# supply-protection.net
KiCad netlist of a schematic drawn in Altium Designer
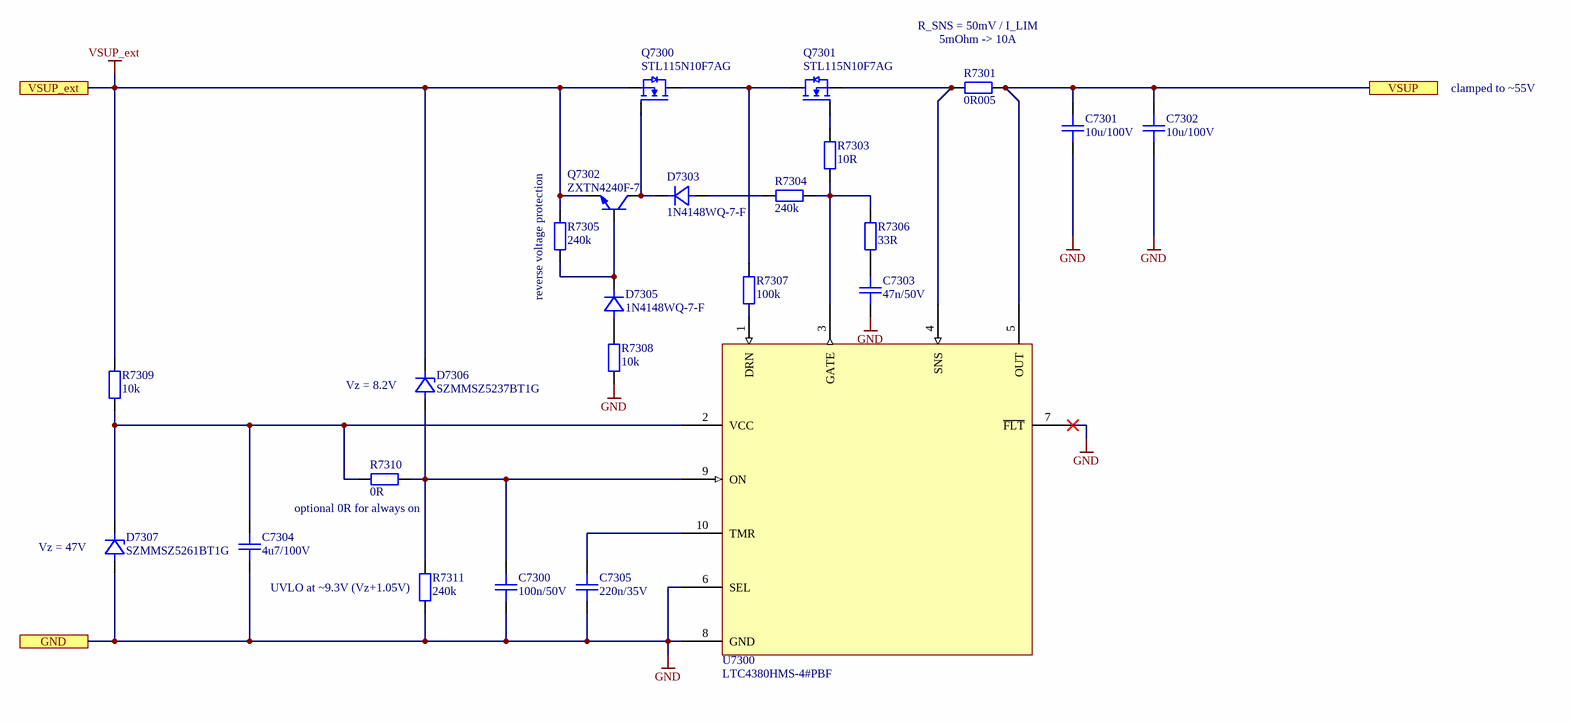
[diagram p0: supply-protection.SchDoc]

(export (version "E")
  (design (tool "Eeschema 10.0.6"))
  (components
    (comp (ref "C7300")
      (value "100n/50V")
      (footprint "CAPC1005X06N")
      (description "MLCC")
      (fields (field (name "PART NUMBER") "gen_C_ceramic_100n_50V_X7R_0402"))
      (libsource (lib "OE750") (part "C"))
    )
    (comp (ref "C7301")
      (value "10u/100V")
      (footprint "CAPC5750X28N")
      (description "MLCC")
      (fields (field (name "PART NUMBER") "gen_C_ceramic_10u_100V_X7S_2220"))
      (libsource (lib "OE750") (part "C"))
    )
    (comp (ref "C7302")
      (value "10u/100V")
      (footprint "CAPC5750X28N")
      (description "MLCC")
      (fields (field (name "PART NUMBER") "gen_C_ceramic_10u_100V_X7S_2220"))
      (libsource (lib "OE750") (part "C"))
    )
    (comp (ref "C7303")
      (value "47n/50V")
      (footprint "CAPC1005X06N")
      (description "MLCC")
      (fields (field (name "PART NUMBER") "gen_C_ceramic_47n_50V_X7R_0402"))
      (libsource (lib "OE750") (part "C"))
    )
    (comp (ref "C7304")
      (value "4u7/100V")
      (footprint "CAPC3225X25N")
      (description "MLCC")
      (fields (field (name "PART NUMBER") "gen_C_ceramic_4u7_100V_X7S_1210"))
      (libsource (lib "OE750") (part "C"))
    )
    (comp (ref "C7305")
      (value "220n/35V")
      (footprint "CAPC1005X06N")
      (description "MLCC")
      (fields (field (name "PART NUMBER") "gen_C_ceramic_220n_35V_X7R_0402"))
      (libsource (lib "OE750") (part "C"))
    )
    (comp (ref "D7303")
      (value "1N4148WQ-7-F")
      (footprint "SOD-123_CASE-425-04-ISSUE-G")
      (description "Diode")
      (fields (field (name "MANUFACTURER") "Diodes Inc."))
      (libsource (lib "OE750") (part "D"))
    )
    (comp (ref "D7305")
      (value "1N4148WQ-7-F")
      (footprint "SOD-123_CASE-425-04-ISSUE-G")
      (description "Diode")
      (fields (field (name "MANUFACTURER") "Diodes Inc."))
      (libsource (lib "OE750") (part "D"))
    )
    (comp (ref "D7306")
      (value "SZMMSZ5237BT1G")
      (footprint "SOD-123_CASE-425-04-ISSUE-G")
      (description "Zener Diode")
      (fields (field (name "MANUFACTURER") "ON Semiconductor"))
      (libsource (lib "OE750") (part "D_Zener"))
    )
    (comp (ref "D7307")
      (value "SZMMSZ5261BT1G")
      (footprint "SOD-123_CASE-425-04-ISSUE-G")
      (description "Zener Diode")
      (fields (field (name "MANUFACTURER") "ON Semiconductor"))
      (libsource (lib "OE750") (part "D_Zener"))
    )
    (comp (ref "Q7300")
      (value "STL115N10F7AG")
      (footprint "ST_PowerFLAT_5x6_WF_type_C")
      (description "N-Channel MOSFET, 100 V, 107 A, 5 mOhm")
      (fields (field (name "MANUFACTURER") "STMicroelectronics"))
      (libsource (lib "OE750") (part "NMOS"))
    )
    (comp (ref "Q7301")
      (value "STL115N10F7AG")
      (footprint "ST_PowerFLAT_5x6_WF_type_C")
      (description "N-Channel MOSFET, 100 V, 107 A, 5 mOhm")
      (fields (field (name "MANUFACTURER") "STMicroelectronics"))
      (libsource (lib "OE750") (part "NMOS"))
    )
    (comp (ref "Q7302")
      (value "ZXTN4240F-7")
      (footprint "DIODES_SOT23_NPN")
      (description "Single NPN Transistor")
      (fields (field (name "MANUFACTURER") "Diodes Inc."))
      (libsource (lib "OE750") (part "NPN"))
    )
    (comp (ref "R7301")
      (value "0R005")
      (footprint "PANASONIC_ERJMS4H")
      (description "SMD Shunt Resistor 0R005")
      (fields (field (name "PART NUMBER") "ERJ-MS4HF5M0U") (field (name "TOLERANCE") "1%"))
      (libsource (lib "OE750") (part "R"))
    )
    (comp (ref "R7303")
      (value "10R")
      (footprint "RESC1005X04N")
      (description "SMD Resistor 10R 0402")
      (fields (field (name "PART NUMBER") "gen_R_10R_0402") (field (name "TOLERANCE") "1%"))
      (libsource (lib "OE750") (part "R"))
    )
    (comp (ref "R7304")
      (value "240k")
      (footprint "RESC1005X04N")
      (description "SMD Resistor 240k 0402")
      (fields (field (name "PART NUMBER") "gen_R_240k_0402") (field (name "TOLERANCE") "1%"))
      (libsource (lib "OE750") (part "R"))
    )
    (comp (ref "R7305")
      (value "240k")
      (footprint "RESC1005X04N")
      (description "SMD Resistor 240k 0402")
      (fields (field (name "PART NUMBER") "gen_R_240k_0402") (field (name "TOLERANCE") "1%"))
      (libsource (lib "OE750") (part "R"))
    )
    (comp (ref "R7306")
      (value "33R")
      (footprint "RESC1005X04N")
      (description "SMD Resistor 33R 0402")
      (fields (field (name "PART NUMBER") "gen_R_33R_0402") (field (name "TOLERANCE") "1%"))
      (libsource (lib "OE750") (part "R"))
    )
    (comp (ref "R7307")
      (value "100k")
      (footprint "RESC1005X04N")
      (description "SMD Resistor 100k 0402")
      (fields (field (name "PART NUMBER") "gen_R_100k_0402") (field (name "TOLERANCE") "1%"))
      (libsource (lib "OE750") (part "R"))
    )
    (comp (ref "R7308")
      (value "10k")
      (footprint "RESC1005X04N")
      (description "SMD Resistor 10k 0402")
      (fields (field (name "PART NUMBER") "gen_R_10k_0402") (field (name "TOLERANCE") "1%"))
      (libsource (lib "OE750") (part "R"))
    )
    (comp (ref "R7309")
      (value "10k")
      (footprint "RESC1005X04N")
      (description "SMD Resistor 10k 0402")
      (fields (field (name "PART NUMBER") "gen_R_10k_0402") (field (name "TOLERANCE") "1%"))
      (libsource (lib "OE750") (part "R"))
    )
    (comp (ref "R7310")
      (value "0R")
      (footprint "RESC1005X04N")
      (description "SMD Resistor 0R 0402")
      (fields (field (name "PART NUMBER") "gen_R_0R_0402") (field (name "POWER") "0.063W"))
      (libsource (lib "OE750") (part "R"))
    )
    (comp (ref "R7311")
      (value "240k")
      (footprint "RESC1005X04N")
      (description "SMD Resistor 240k 0402")
      (fields (field (name "PART NUMBER") "gen_R_240k_0402") (field (name "TOLERANCE") "1%"))
      (libsource (lib "OE750") (part "R"))
    )
    (comp (ref "U7300")
      (value "LTC4380HMS-4#PBF")
      (footprint "LTC4380-MSOP10")
      (description "Low Quiescent Current Surge Stopper")
      (fields (field (name "MANUFACTURER") "Analog Devices"))
      (libsource (lib "OE750") (part "LTC4380"))
    )
  )
  (nets
    (net (code "1") (name "/VSUP") (class "Default")
      (node (ref "C7301") (pin "2") (pinfunction "2_2") (pintype "passive"))
      (node (ref "C7302") (pin "2") (pinfunction "2_2") (pintype "passive"))
      (node (ref "R7301") (pin "2") (pinfunction "2_2") (pintype "passive"))
      (node (ref "U7300") (pin "5") (pinfunction "OUT_5") (pintype "power_in"))
    )
    (net (code "2") (name "GND") (class "Default")
      (node (ref "C7300") (pin "2") (pinfunction "2_2") (pintype "passive"))
      (node (ref "C7301") (pin "1") (pinfunction "1_1") (pintype "passive"))
      (node (ref "C7302") (pin "1") (pinfunction "1_1") (pintype "passive"))
      (node (ref "C7303") (pin "1") (pinfunction "1_1") (pintype "passive"))
      (node (ref "C7304") (pin "1") (pinfunction "1_1") (pintype "passive"))
      (node (ref "C7305") (pin "1") (pinfunction "1_1") (pintype "passive"))
      (node (ref "D7307") (pin "2") (pinfunction "A_2") (pintype "passive"))
      (node (ref "R7308") (pin "1") (pinfunction "1_1") (pintype "passive"))
      (node (ref "R7311") (pin "1") (pinfunction "1_1") (pintype "passive"))
      (node (ref "U7300") (pin "6") (pinfunction "SEL_6") (pintype "passive"))
      (node (ref "U7300") (pin "7") (pinfunction "FLT_7") (pintype "open_collector"))
      (node (ref "U7300") (pin "8") (pinfunction "GND_8") (pintype "power_in"))
    )
    (net (code "3") (name "Net-(C7303-Pad2)") (class "Default")
      (node (ref "C7303") (pin "2") (pinfunction "2_2") (pintype "passive"))
      (node (ref "R7306") (pin "1") (pinfunction "1_1") (pintype "passive"))
    )
    (net (code "4") (name "Net-(D7303-A)") (class "Default")
      (node (ref "D7303") (pin "2") (pinfunction "A_2") (pintype "passive"))
      (node (ref "R7304") (pin "2") (pinfunction "2_2") (pintype "passive"))
    )
    (net (code "5") (name "Net-(D7303-K)") (class "Default")
      (node (ref "D7303") (pin "1") (pinfunction "K_1") (pintype "passive"))
      (node (ref "Q7300") (pin "G") (pinfunction "G_G") (pintype "passive"))
      (node (ref "Q7302") (pin "C") (pinfunction "C_C") (pintype "passive"))
    )
    (net (code "6") (name "Net-(D7305-A)") (class "Default")
      (node (ref "D7305") (pin "2") (pinfunction "A_2") (pintype "passive"))
      (node (ref "R7308") (pin "2") (pinfunction "2_2") (pintype "passive"))
    )
    (net (code "7") (name "Net-(D7305-K)") (class "Default")
      (node (ref "D7305") (pin "1") (pinfunction "K_1") (pintype "passive"))
      (node (ref "Q7302") (pin "B") (pinfunction "B_B") (pintype "passive"))
      (node (ref "R7305") (pin "1") (pinfunction "1_1") (pintype "passive"))
    )
    (net (code "8") (name "Net-(D7306-A)") (class "Default")
      (node (ref "C7300") (pin "1") (pinfunction "1_1") (pintype "passive"))
      (node (ref "D7306") (pin "2") (pinfunction "A_2") (pintype "passive"))
      (node (ref "R7310") (pin "1") (pinfunction "1_1") (pintype "passive"))
      (node (ref "R7311") (pin "2") (pinfunction "2_2") (pintype "passive"))
      (node (ref "U7300") (pin "9") (pinfunction "ON_9") (pintype "input"))
    )
    (net (code "9") (name "Net-(D7307-K)") (class "Default")
      (node (ref "C7304") (pin "2") (pinfunction "2_2") (pintype "passive"))
      (node (ref "D7307") (pin "1") (pinfunction "K_1") (pintype "passive"))
      (node (ref "R7309") (pin "1") (pinfunction "1_1") (pintype "passive"))
      (node (ref "R7310") (pin "2") (pinfunction "2_2") (pintype "passive"))
      (node (ref "U7300") (pin "2") (pinfunction "VCC_2") (pintype "power_in"))
    )
    (net (code "10") (name "Net-(Q7300-PadD)") (class "Default")
      (node (ref "Q7300") (pin "D") (pinfunction "D_D") (pintype "passive"))
      (node (ref "Q7301") (pin "D") (pinfunction "D_D") (pintype "passive"))
      (node (ref "R7307") (pin "2") (pinfunction "2_2") (pintype "passive"))
    )
    (net (code "11") (name "Net-(Q7301-PadG)") (class "Default")
      (node (ref "Q7301") (pin "G") (pinfunction "G_G") (pintype "passive"))
      (node (ref "R7303") (pin "2") (pinfunction "2_2") (pintype "passive"))
    )
    (net (code "12") (name "Net-(U7300-DRN)") (class "Default")
      (node (ref "R7307") (pin "1") (pinfunction "1_1") (pintype "passive"))
      (node (ref "U7300") (pin "1") (pinfunction "DRN_1") (pintype "input"))
    )
    (net (code "13") (name "Net-(U7300-GATE)") (class "Default")
      (node (ref "R7303") (pin "1") (pinfunction "1_1") (pintype "passive"))
      (node (ref "R7304") (pin "1") (pinfunction "1_1") (pintype "passive"))
      (node (ref "R7306") (pin "2") (pinfunction "2_2") (pintype "passive"))
      (node (ref "U7300") (pin "3") (pinfunction "GATE_3") (pintype "output"))
    )
    (net (code "14") (name "Net-(U7300-SNS)") (class "Default")
      (node (ref "Q7301") (pin "S") (pinfunction "S_S") (pintype "passive"))
      (node (ref "R7301") (pin "1") (pinfunction "1_1") (pintype "passive"))
      (node (ref "U7300") (pin "4") (pinfunction "SNS_4") (pintype "input"))
    )
    (net (code "15") (name "Net-(U7300-TMR)") (class "Default")
      (node (ref "C7305") (pin "2") (pinfunction "2_2") (pintype "passive"))
      (node (ref "U7300") (pin "10") (pinfunction "TMR_10") (pintype "passive"))
    )
    (net (code "16") (name "VSUP_ext") (class "Default")
      (node (ref "D7306") (pin "1") (pinfunction "K_1") (pintype "passive"))
      (node (ref "Q7300") (pin "S") (pinfunction "S_S") (pintype "passive"))
      (node (ref "Q7302") (pin "E") (pinfunction "E_E") (pintype "passive"))
      (node (ref "R7305") (pin "2") (pinfunction "2_2") (pintype "passive"))
      (node (ref "R7309") (pin "2") (pinfunction "2_2") (pintype "passive"))
    )
  )
)
